# 48VSensing.net
KiCad netlist of a schematic drawn in Altium Designer
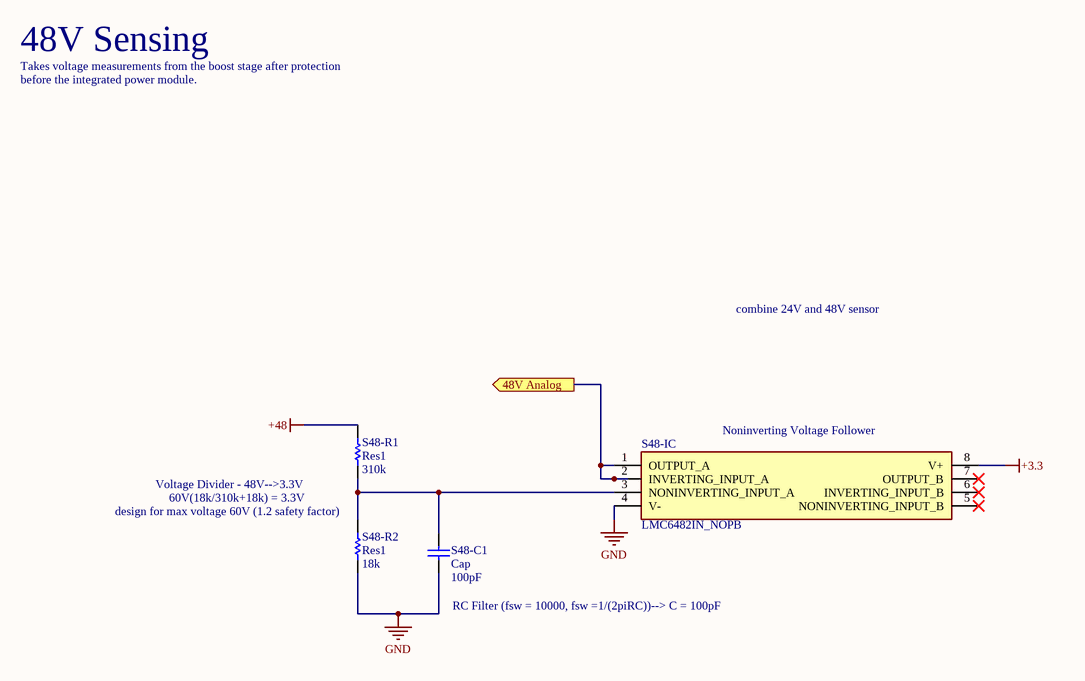
[diagram p0: 48VSensing.SchDoc]

(export (version "E")
  (design (tool "Eeschema 10.0.6"))
  (components
    (comp (ref "S48-C1")
      (value "Cap")
      (footprint "RAD-0.3")
      (description "Capacitor")
      (fields (field (name "ALTIUM_VALUE") "100pF") (field (name "PUBLISHER") "Altium Limited"))
      (libsource (lib "Miscellaneous Devices") (part "Cap"))
    )
    (comp (ref "S48-IC")
      (value "LMC6482IN_NOPB")
      (footprint "SamacSys:DIP794W53P254L959H508Q8N")
      (description "Integrated Circuit")
      (fields
        (field (name "MANUFACTURER_PART_NUMBER") "LMC6482IN/NOPB")
        (field (name "MOUSER PART NUMBER") "926-LMC6482IN/NOPB")
      )
      (libsource (lib "*") (part "LMC6482IN_NOPB"))
    )
    (comp (ref "S48-R1")
      (value "Res1")
      (footprint "AXIAL-0.3")
      (description "Resistor")
      (fields (field (name "ALTIUM_VALUE") "310k") (field (name "PUBLISHER") "Altium Limited"))
      (libsource (lib "Miscellaneous Devices") (part "Res1"))
    )
    (comp (ref "S48-R2")
      (value "Res1")
      (footprint "AXIAL-0.3")
      (description "Resistor")
      (fields (field (name "ALTIUM_VALUE") "18k") (field (name "PUBLISHER") "Altium Limited"))
      (libsource (lib "Miscellaneous Devices") (part "Res1"))
    )
  )
  (nets
    (net (code "1") (name "+3.3") (class "Default")
      (node (ref "S48-IC") (pin "8") (pinfunction "V+_8") (pintype "passive"))
    )
    (net (code "2") (name "+48") (class "Default")
      (node (ref "S48-R1") (pin "2") (pinfunction "2_2") (pintype "passive"))
    )
    (net (code "3") (name "/48V Analog") (class "Default")
      (node (ref "S48-IC") (pin "1") (pinfunction "OUTPUT_A_1") (pintype "passive"))
      (node (ref "S48-IC") (pin "2") (pinfunction "INVERTING_INPUT_A_2") (pintype "passive"))
    )
    (net (code "4") (name "GND") (class "Default")
      (node (ref "S48-C1") (pin "1") (pinfunction "1_1") (pintype "passive"))
      (node (ref "S48-IC") (pin "4") (pinfunction "V-_4") (pintype "passive"))
      (node (ref "S48-R2") (pin "1") (pinfunction "1_1") (pintype "passive"))
    )
    (net (code "5") (name "Net-(S48-IC-NONINVERTING_INPUT_A)") (class "Default")
      (node (ref "S48-C1") (pin "2") (pinfunction "2_2") (pintype "passive"))
      (node (ref "S48-IC") (pin "3") (pinfunction "NONINVERTING_INPUT_A_3") (pintype "passive"))
      (node (ref "S48-R1") (pin "1") (pinfunction "1_1") (pintype "passive"))
      (node (ref "S48-R2") (pin "2") (pinfunction "2_2") (pintype "passive"))
    )
    (net (code "6") (name "unconnected-(S48-IC-INVERTING_INPUT_B-Pad6)") (class "Default")
      (node (ref "S48-IC") (pin "6") (pinfunction "INVERTING_INPUT_B_6") (pintype "passive+no_connect"))
    )
    (net (code "7") (name "unconnected-(S48-IC-NONINVERTING_INPUT_B-Pad5)") (class "Default")
      (node (ref "S48-IC") (pin "5") (pinfunction "NONINVERTING_INPUT_B_5") (pintype "passive+no_connect"))
    )
    (net (code "8") (name "unconnected-(S48-IC-OUTPUT_B-Pad7)") (class "Default")
      (node (ref "S48-IC") (pin "7") (pinfunction "OUTPUT_B_7") (pintype "passive+no_connect"))
    )
  )
)
